# lucid_glasses.net
KiCad netlist of a schematic drawn in EAGLE
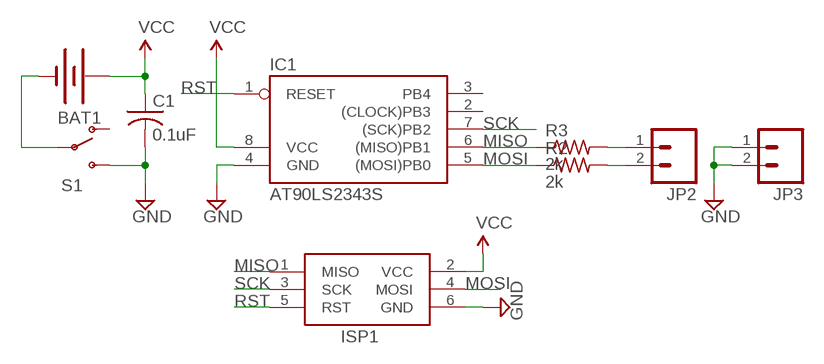
[diagram p0: schematic, sheet 1]

(export (version "E")
  (design (tool "Eeschema 10.0.6"))
  (components
    (comp (ref "BAT1")
      (value "BATTERY20SMD")
      (footprint "eagle-import:BATTCON_20MM")
      (libsource (lib "eagle-import") (part "BATTERY20SMD"))
    )
    (comp (ref "C1")
      (value "0.1uF")
      (footprint "eagle-import:C1206")
      (libsource (lib "eagle-import") (part "C-USC1206"))
    )
    (comp (ref "IC1")
      (value "AT90LS2343S")
      (footprint "eagle-import:SOIC8")
      (libsource (lib "eagle-import") (part "AT902343SLS"))
    )
    (comp (ref "ISP1")
      (value "AVRISP-6")
      (footprint "eagle-import:AVRISP")
      (libsource (lib "eagle-import") (part "AVRISP-6"))
    )
    (comp (ref "JP2")
      (value "M02PTH")
      (footprint "eagle-import:1X02")
      (libsource (lib "eagle-import") (part "M02PTH"))
    )
    (comp (ref "JP3")
      (value "M02PTH")
      (footprint "eagle-import:1X02")
      (libsource (lib "eagle-import") (part "M02PTH"))
    )
    (comp (ref "R2")
      (value "2k")
      (footprint "eagle-import:R1206")
      (libsource (lib "eagle-import") (part "R-US_R1206"))
    )
    (comp (ref "R3")
      (value "2k")
      (footprint "eagle-import:R1206")
      (libsource (lib "eagle-import") (part "R-US_R1206"))
    )
    (comp (ref "S1")
      (value "SWITCH-SPSTSMD2")
      (footprint "eagle-import:SWITCH-SPDT-SMD")
      (libsource (lib "eagle-import") (part "SWITCH-SPSTSMD2"))
    )
  )
  (nets
    (net (code "1") (name "/MISO") (class "Default")
      (node (ref "IC1") (pin "6") (pinfunction "(MISO)PB1_6") (pintype "bidirectional"))
      (node (ref "ISP1") (pin "1") (pinfunction "MISO_1") (pintype "input"))
      (node (ref "R3") (pin "1") (pinfunction "1_1") (pintype "passive"))
    )
    (net (code "2") (name "/MOSI") (class "Default")
      (node (ref "IC1") (pin "5") (pinfunction "(MOSI)PB0_5") (pintype "bidirectional"))
      (node (ref "ISP1") (pin "4") (pinfunction "MOSI_4") (pintype "output"))
      (node (ref "R2") (pin "1") (pinfunction "1_1") (pintype "passive"))
    )
    (net (code "3") (name "/RST") (class "Default")
      (node (ref "IC1") (pin "1") (pinfunction "RESET_1") (pintype "input"))
      (node (ref "ISP1") (pin "5") (pinfunction "RST_5") (pintype "output"))
    )
    (net (code "4") (name "/SCK") (class "Default")
      (node (ref "IC1") (pin "7") (pinfunction "(SCK)PB2_7") (pintype "bidirectional"))
      (node (ref "ISP1") (pin "3") (pinfunction "SCK_3") (pintype "output"))
    )
    (net (code "5") (name "GND") (class "Default")
      (node (ref "C1") (pin "2") (pinfunction "2_2") (pintype "passive"))
      (node (ref "IC1") (pin "4") (pinfunction "GND_4") (pintype "power_in"))
      (node (ref "ISP1") (pin "6") (pinfunction "GND_6") (pintype "power_in"))
      (node (ref "JP3") (pin "1") (pinfunction "1_1") (pintype "passive"))
      (node (ref "JP3") (pin "2") (pinfunction "2_2") (pintype "passive"))
      (node (ref "S1") (pin "3") (pinfunction "S_3") (pintype "passive"))
    )
    (net (code "6") (name "Net-(BAT1--)") (class "Default")
      (node (ref "BAT1") (pin "2") (pinfunction "-_2") (pintype "power_in"))
      (node (ref "S1") (pin "2") (pinfunction "P_2") (pintype "passive"))
    )
    (net (code "7") (name "Net-(JP2-Pad1)") (class "Default")
      (node (ref "JP2") (pin "1") (pinfunction "1_1") (pintype "passive"))
      (node (ref "R3") (pin "2") (pinfunction "2_2") (pintype "passive"))
    )
    (net (code "8") (name "Net-(JP2-Pad2)") (class "Default")
      (node (ref "JP2") (pin "2") (pinfunction "2_2") (pintype "passive"))
      (node (ref "R2") (pin "2") (pinfunction "2_2") (pintype "passive"))
    )
    (net (code "9") (name "VCC") (class "Default")
      (node (ref "BAT1") (pin "1") (pinfunction "+_1") (pintype "power_in"))
      (node (ref "C1") (pin "1") (pinfunction "1_1") (pintype "passive"))
      (node (ref "IC1") (pin "8") (pinfunction "VCC_8") (pintype "power_in"))
      (node (ref "ISP1") (pin "2") (pinfunction "VCC_2") (pintype "power_in"))
    )
    (net (code "10") (name "unconnected-(IC1-(CLOCK)PB3-Pad2)") (class "Default")
      (node (ref "IC1") (pin "2") (pinfunction "(CLOCK)PB3_2") (pintype "bidirectional"))
    )
    (net (code "11") (name "unconnected-(IC1-PB4-Pad3)") (class "Default")
      (node (ref "IC1") (pin "3") (pinfunction "PB4_3") (pintype "bidirectional"))
    )
    (net (code "12") (name "unconnected-(S1-O-Pad1)") (class "Default")
      (node (ref "S1") (pin "1") (pinfunction "O_1") (pintype "passive"))
    )
  )
)
